# samrtbox.net
KiCad netlist of a schematic drawn in Altium Designer
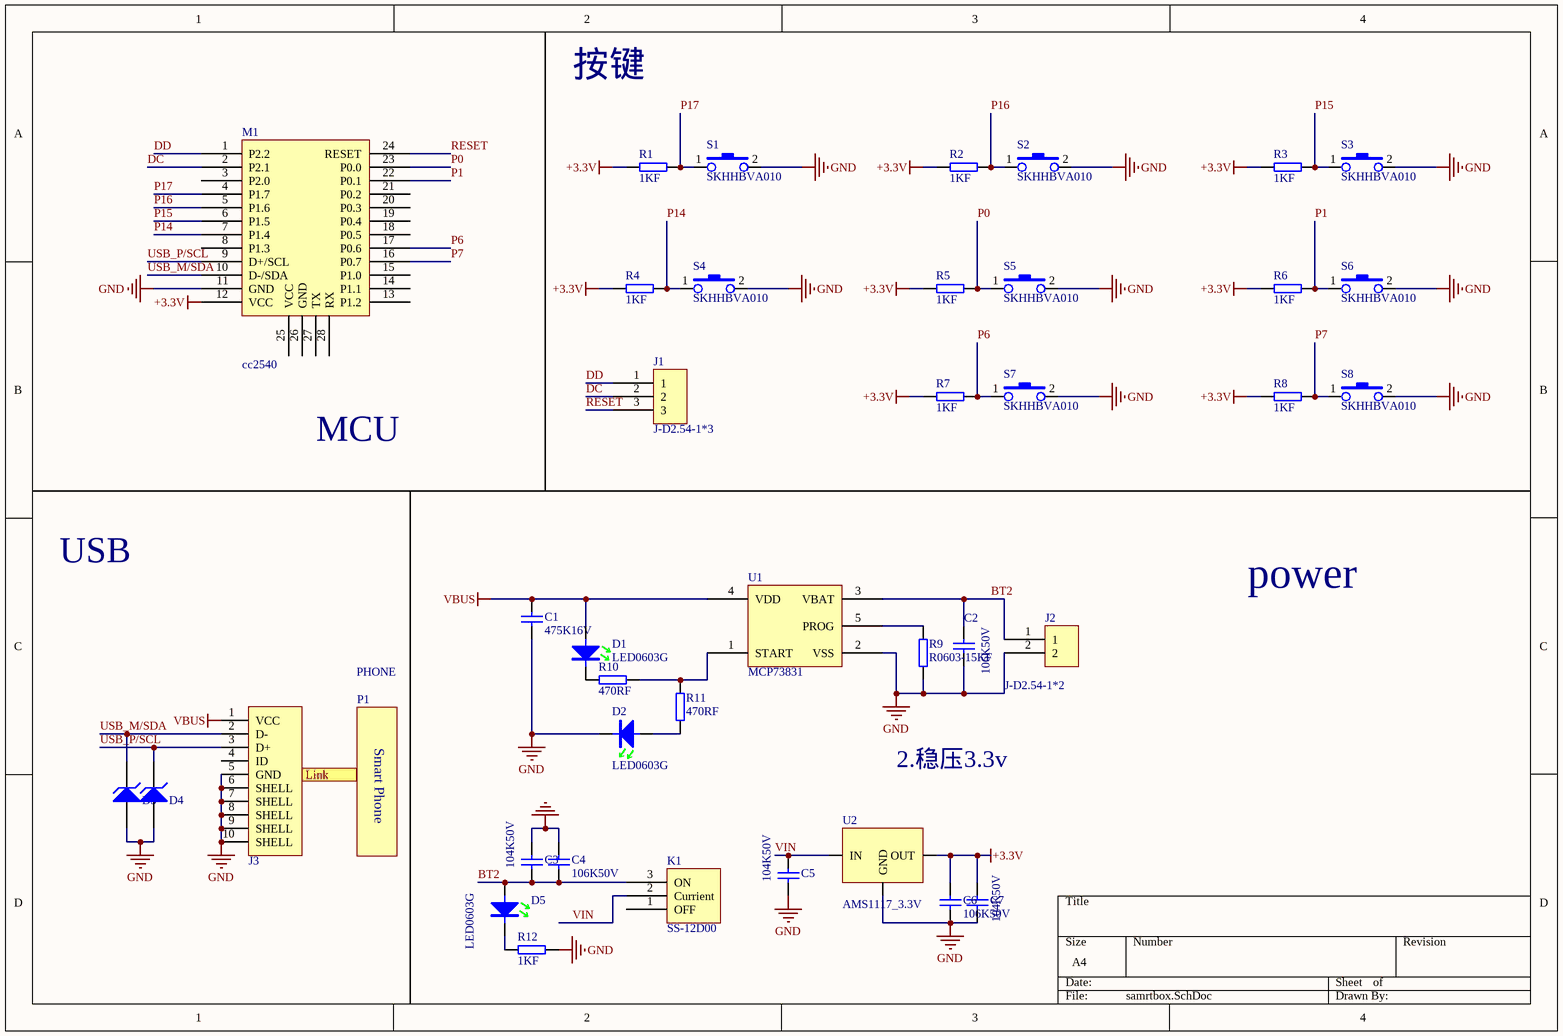
[diagram p0: samrtbox.SchDoc]

(export (version "E")
  (design (tool "Eeschema 10.0.6"))
  (components
    (comp (ref "C1")
      (value "475K16V")
      (footprint "C0603")
      (description "贴片电容-陶瓷")
      (libsource (lib "Capacitor") (part "C0603X7R-475K16V"))
    )
    (comp (ref "C2")
      (value "106K50V")
      (footprint "C0603")
      (description "贴片电容-陶瓷")
      (libsource (lib "Capacitor") (part "C0603X7R-106K50V"))
    )
    (comp (ref "C3")
      (value "104K50V")
      (footprint "C0603")
      (description "贴片电容-陶瓷")
      (libsource (lib "Capacitor") (part "C0603X7R-104K50V"))
    )
    (comp (ref "C4")
      (value "106K50V")
      (footprint "C0603")
      (description "贴片电容-陶瓷")
      (libsource (lib "Capacitor") (part "C0603X7R-106K50V"))
    )
    (comp (ref "C5")
      (value "104K50V")
      (footprint "C0603")
      (description "贴片电容-陶瓷")
      (libsource (lib "Capacitor") (part "C0603X7R-104K50V"))
    )
    (comp (ref "C6")
      (value "106K50V")
      (footprint "C0603")
      (description "贴片电容-陶瓷")
      (libsource (lib "Capacitor") (part "C0603X7R-106K50V"))
    )
    (comp (ref "C7")
      (value "104K50V")
      (footprint "C0603")
      (description "贴片电容-陶瓷")
      (libsource (lib "Capacitor") (part "C0603X7R-104K50V"))
    )
    (comp (ref "D1")
      (value "LED0603G")
      (footprint "D-LED0603G")
      (description "贴片二极管-LED")
      (libsource (lib "Diode") (part "DLED-0603-G"))
    )
    (comp (ref "D2")
      (value "LED0603G")
      (footprint "D-LED0603G")
      (description "贴片二极管-LED")
      (libsource (lib "Diode") (part "DLED-0603-G"))
    )
    (comp (ref "D3")
      (value "ESDA_TR1/0603")
      (footprint "HS_0603D")
      (description "Zener Diode")
      (fields (field (name "PUBLISHER") "*"))
      (libsource (lib "aiwacV2.0") (part "D Zener"))
    )
    (comp (ref "D4")
      (value "ESDA_TR1/0603")
      (footprint "HS_0603D")
      (description "Zener Diode")
      (fields (field (name "PUBLISHER") "*"))
      (libsource (lib "aiwacV2.0") (part "D Zener"))
    )
    (comp (ref "D5")
      (value "LED0603G")
      (footprint "D-LED0603G")
      (description "贴片二极管-LED")
      (libsource (lib "aiwacV2.0") (part "DLED-0603-G"))
    )
    (comp (ref "J1")
      (value "J-D2.54-1*3")
      (footprint "D2.54-1*3P")
      (libsource (lib "Connector") (part "J-D2.54-1*3单排"))
    )
    (comp (ref "J2")
      (value "J-D2.54-1*2")
      (footprint "D2.54-1*2P")
      (libsource (lib "Connector") (part "J-D2.54-1*2单排"))
    )
    (comp (ref "J3")
      (value "USB-MINI-SOCKET")
      (footprint "MICRO-USB - 5.9")
      (description "USB-A卧式插座")
      (libsource (lib "epic2") (part "J-USB-MINI-SOCKET"))
    )
    (comp (ref "K1")
      (value "SS-12D00")
      (footprint "SS-12D00")
      (libsource (lib "Key") (part "SS-12D00(1P2T) 立式 柄高5MM"))
    )
    (comp (ref "M1") (value "cc2540") (footprint "CC25XXSM") (libsource (lib "diapers1") (part "cc2540")))
    (comp (ref "P1") (value "PHONE") (libsource (lib "epic") (part "PHONE")))
    (comp (ref "R1")
      (value "1KF")
      (footprint "R0603")
      (description "贴片电阻-通用")
      (libsource (lib "diapers_1") (part "R0603-1KF"))
    )
    (comp (ref "R2")
      (value "1KF")
      (footprint "R0603")
      (description "贴片电阻-通用")
      (libsource (lib "diapers_1") (part "R0603-1KF"))
    )
    (comp (ref "R3")
      (value "1KF")
      (footprint "R0603")
      (description "贴片电阻-通用")
      (libsource (lib "diapers_1") (part "R0603-1KF"))
    )
    (comp (ref "R4")
      (value "1KF")
      (footprint "R0603")
      (description "贴片电阻-通用")
      (libsource (lib "diapers_1") (part "R0603-1KF"))
    )
    (comp (ref "R5")
      (value "1KF")
      (footprint "R0603")
      (description "贴片电阻-通用")
      (libsource (lib "diapers_1") (part "R0603-1KF"))
    )
    (comp (ref "R6")
      (value "1KF")
      (footprint "R0603")
      (description "贴片电阻-通用")
      (libsource (lib "diapers_1") (part "R0603-1KF"))
    )
    (comp (ref "R7")
      (value "1KF")
      (footprint "R0603")
      (description "贴片电阻-通用")
      (libsource (lib "diapers_1") (part "R0603-1KF"))
    )
    (comp (ref "R8")
      (value "1KF")
      (footprint "R0603")
      (description "贴片电阻-通用")
      (libsource (lib "diapers_1") (part "R0603-1KF"))
    )
    (comp (ref "R9")
      (value "R0603-15KF")
      (footprint "R0603")
      (description "贴片电容-通用")
      (libsource (lib "Resistor") (part "R0603-15KF"))
    )
    (comp (ref "R10")
      (value "470RF")
      (footprint "R0603")
      (description "贴片电阻-通用")
      (libsource (lib "Resistor") (part "R0603-470RF"))
    )
    (comp (ref "R11")
      (value "470RF")
      (footprint "R0603")
      (description "贴片电阻-通用")
      (libsource (lib "Resistor") (part "R0603-470RF"))
    )
    (comp (ref "R12")
      (value "1KF")
      (footprint "R0603")
      (description "贴片电阻-通用")
      (libsource (lib "Resistor") (part "R0603-1KF"))
    )
    (comp (ref "S1")
      (value "SKHHBVA010")
      (footprint "S-SKHHBVA010")
      (description "轻触按键")
      (libsource (lib "Key") (part "S-SKHHBVA010"))
    )
    (comp (ref "S2")
      (value "SKHHBVA010")
      (footprint "S-SKHHBVA010")
      (description "轻触按键")
      (libsource (lib "Key") (part "S-SKHHBVA010"))
    )
    (comp (ref "S3")
      (value "SKHHBVA010")
      (footprint "S-SKHHBVA010")
      (description "轻触按键")
      (libsource (lib "Key") (part "S-SKHHBVA010"))
    )
    (comp (ref "S4")
      (value "SKHHBVA010")
      (footprint "S-SKHHBVA010")
      (description "轻触按键")
      (libsource (lib "Key") (part "S-SKHHBVA010"))
    )
    (comp (ref "S5")
      (value "SKHHBVA010")
      (footprint "S-SKHHBVA010")
      (description "轻触按键")
      (libsource (lib "Key") (part "S-SKHHBVA010"))
    )
    (comp (ref "S6")
      (value "SKHHBVA010")
      (footprint "S-SKHHBVA010")
      (description "轻触按键")
      (libsource (lib "Key") (part "S-SKHHBVA010"))
    )
    (comp (ref "S7")
      (value "SKHHBVA010")
      (footprint "S-SKHHBVA010")
      (description "轻触按键")
      (libsource (lib "Key") (part "S-SKHHBVA010"))
    )
    (comp (ref "S8")
      (value "SKHHBVA010")
      (footprint "S-SKHHBVA010")
      (description "轻触按键")
      (libsource (lib "Key") (part "S-SKHHBVA010"))
    )
    (comp (ref "U1")
      (value "MCP73831")
      (footprint "SOT23-5N")
      (description "charge IC")
      (libsource (lib "IC") (part "MCP73831"))
    )
    (comp (ref "U2")
      (value "AMS1117_3.3V")
      (footprint "SOT-223")
      (libsource (lib "IC") (part "AMS1117-3.3V"))
    )
  )
  (nets
    (net (code "1") (name "+3.3V") (class "Default")
      (node (ref "C6") (pin "2") (pinfunction "2_2") (pintype "passive"))
      (node (ref "C7") (pin "1") (pinfunction "1_1") (pintype "passive"))
      (node (ref "M1") (pin "12") (pinfunction "VCC_12") (pintype "passive"))
      (node (ref "R1") (pin "1") (pinfunction "1_1") (pintype "passive"))
      (node (ref "R2") (pin "1") (pinfunction "1_1") (pintype "passive"))
      (node (ref "R3") (pin "1") (pinfunction "1_1") (pintype "passive"))
      (node (ref "R4") (pin "1") (pinfunction "1_1") (pintype "passive"))
      (node (ref "R5") (pin "1") (pinfunction "1_1") (pintype "passive"))
      (node (ref "R6") (pin "1") (pinfunction "1_1") (pintype "passive"))
      (node (ref "R7") (pin "1") (pinfunction "1_1") (pintype "passive"))
      (node (ref "R8") (pin "1") (pinfunction "1_1") (pintype "passive"))
      (node (ref "U2") (pin "2") (pinfunction "OUT_2") (pintype "passive"))
    )
    (net (code "2") (name "/BT2") (class "Default")
      (node (ref "C2") (pin "1") (pinfunction "1_1") (pintype "passive"))
      (node (ref "C3") (pin "2") (pinfunction "2_2") (pintype "passive"))
      (node (ref "C4") (pin "1") (pinfunction "1_1") (pintype "passive"))
      (node (ref "D5") (pin "1") (pinfunction "1_1") (pintype "passive"))
      (node (ref "J2") (pin "1") (pinfunction "1_1") (pintype "passive"))
      (node (ref "K1") (pin "3") (pinfunction "ON_3") (pintype "passive"))
      (node (ref "U1") (pin "3") (pinfunction "VBAT_3") (pintype "passive"))
    )
    (net (code "3") (name "/DC") (class "Default")
      (node (ref "J1") (pin "2") (pinfunction "2_2") (pintype "passive"))
      (node (ref "M1") (pin "2") (pinfunction "P2.1_2") (pintype "passive"))
    )
    (net (code "4") (name "/DD") (class "Default")
      (node (ref "J1") (pin "1") (pinfunction "1_1") (pintype "passive"))
      (node (ref "M1") (pin "1") (pinfunction "P2.2_1") (pintype "passive"))
    )
    (net (code "6") (name "/P0") (class "Default")
      (node (ref "M1") (pin "23") (pinfunction "P0.0_23") (pintype "passive"))
      (node (ref "R5") (pin "2") (pinfunction "2_2") (pintype "passive"))
      (node (ref "S5") (pin "1") (pinfunction "1_1") (pintype "passive"))
    )
    (net (code "7") (name "/P1") (class "Default")
      (node (ref "M1") (pin "22") (pinfunction "P0.1_22") (pintype "passive"))
      (node (ref "R6") (pin "2") (pinfunction "2_2") (pintype "passive"))
      (node (ref "S6") (pin "1") (pinfunction "1_1") (pintype "passive"))
    )
    (net (code "8") (name "/P6") (class "Default")
      (node (ref "M1") (pin "17") (pinfunction "P0.6_17") (pintype "passive"))
      (node (ref "R7") (pin "2") (pinfunction "2_2") (pintype "passive"))
      (node (ref "S7") (pin "1") (pinfunction "1_1") (pintype "passive"))
    )
    (net (code "9") (name "/P7") (class "Default")
      (node (ref "M1") (pin "16") (pinfunction "P0.7_16") (pintype "passive"))
      (node (ref "R8") (pin "2") (pinfunction "2_2") (pintype "passive"))
      (node (ref "S8") (pin "1") (pinfunction "1_1") (pintype "passive"))
    )
    (net (code "10") (name "/P14") (class "Default")
      (node (ref "M1") (pin "7") (pinfunction "P1.4_7") (pintype "passive"))
      (node (ref "R4") (pin "2") (pinfunction "2_2") (pintype "passive"))
      (node (ref "S4") (pin "1") (pinfunction "1_1") (pintype "passive"))
    )
    (net (code "11") (name "/P15") (class "Default")
      (node (ref "M1") (pin "6") (pinfunction "P1.5_6") (pintype "passive"))
      (node (ref "R3") (pin "2") (pinfunction "2_2") (pintype "passive"))
      (node (ref "S3") (pin "1") (pinfunction "1_1") (pintype "passive"))
    )
    (net (code "12") (name "/P16") (class "Default")
      (node (ref "M1") (pin "5") (pinfunction "P1.6_5") (pintype "passive"))
      (node (ref "R2") (pin "2") (pinfunction "2_2") (pintype "passive"))
      (node (ref "S2") (pin "1") (pinfunction "1_1") (pintype "passive"))
    )
    (net (code "13") (name "/P17") (class "Default")
      (node (ref "M1") (pin "4") (pinfunction "P1.7_4") (pintype "passive"))
      (node (ref "R1") (pin "2") (pinfunction "2_2") (pintype "passive"))
      (node (ref "S1") (pin "1") (pinfunction "1_1") (pintype "passive"))
    )
    (net (code "14") (name "/RESET") (class "Default")
      (node (ref "J1") (pin "3") (pinfunction "3_3") (pintype "passive"))
      (node (ref "M1") (pin "24") (pinfunction "RESET_24") (pintype "passive"))
    )
    (net (code "15") (name "/USB_M{slash}SDA") (class "Default")
      (node (ref "D3") (pin "2") (pinfunction "K_2") (pintype "passive"))
      (node (ref "J3") (pin "2") (pinfunction "D-_2") (pintype "passive"))
      (node (ref "M1") (pin "10") (pinfunction "D-/SDA_10") (pintype "passive"))
    )
    (net (code "16") (name "/USB_P{slash}SCL") (class "Default")
      (node (ref "D4") (pin "2") (pinfunction "K_2") (pintype "passive"))
      (node (ref "J3") (pin "3") (pinfunction "D+_3") (pintype "passive"))
      (node (ref "M1") (pin "9") (pinfunction "D+/SCL_9") (pintype "passive"))
    )
    (net (code "17") (name "/VIN") (class "Default")
      (node (ref "C5") (pin "1") (pinfunction "1_1") (pintype "passive"))
      (node (ref "K1") (pin "2") (pinfunction "Currient_2") (pintype "passive"))
      (node (ref "U2") (pin "3") (pinfunction "IN_3") (pintype "passive"))
    )
    (net (code "18") (name "GND") (class "Default")
      (node (ref "C1") (pin "2") (pinfunction "2_2") (pintype "passive"))
      (node (ref "C2") (pin "2") (pinfunction "2_2") (pintype "passive"))
      (node (ref "C3") (pin "1") (pinfunction "1_1") (pintype "passive"))
      (node (ref "C4") (pin "2") (pinfunction "2_2") (pintype "passive"))
      (node (ref "C5") (pin "2") (pinfunction "2_2") (pintype "passive"))
      (node (ref "C6") (pin "1") (pinfunction "1_1") (pintype "passive"))
      (node (ref "C7") (pin "2") (pinfunction "2_2") (pintype "passive"))
      (node (ref "D2") (pin "2") (pinfunction "2_2") (pintype "passive"))
      (node (ref "D3") (pin "1") (pinfunction "A_1") (pintype "passive"))
      (node (ref "D4") (pin "1") (pinfunction "A_1") (pintype "passive"))
      (node (ref "J2") (pin "2") (pinfunction "2_2") (pintype "passive"))
      (node (ref "J3") (pin "10") (pinfunction "SHELL_10") (pintype "passive"))
      (node (ref "J3") (pin "5") (pinfunction "GND_5") (pintype "passive"))
      (node (ref "J3") (pin "6") (pinfunction "SHELL_6") (pintype "passive"))
      (node (ref "J3") (pin "7") (pinfunction "SHELL_7") (pintype "passive"))
      (node (ref "J3") (pin "8") (pinfunction "SHELL_8") (pintype "passive"))
      (node (ref "J3") (pin "9") (pinfunction "SHELL_9") (pintype "passive"))
      (node (ref "M1") (pin "11") (pinfunction "GND_11") (pintype "passive"))
      (node (ref "R12") (pin "2") (pinfunction "2_2") (pintype "passive"))
      (node (ref "R9") (pin "1") (pinfunction "1_1") (pintype "passive"))
      (node (ref "S1") (pin "2") (pinfunction "2_2") (pintype "passive"))
      (node (ref "S2") (pin "2") (pinfunction "2_2") (pintype "passive"))
      (node (ref "S3") (pin "2") (pinfunction "2_2") (pintype "passive"))
      (node (ref "S4") (pin "2") (pinfunction "2_2") (pintype "passive"))
      (node (ref "S5") (pin "2") (pinfunction "2_2") (pintype "passive"))
      (node (ref "S6") (pin "2") (pinfunction "2_2") (pintype "passive"))
      (node (ref "S7") (pin "2") (pinfunction "2_2") (pintype "passive"))
      (node (ref "S8") (pin "2") (pinfunction "2_2") (pintype "passive"))
      (node (ref "U1") (pin "2") (pinfunction "VSS_2") (pintype "passive"))
      (node (ref "U2") (pin "1") (pinfunction "GND_1") (pintype "passive"))
    )
    (net (code "19") (name "Net-(D1-Pad2)") (class "Default")
      (node (ref "D1") (pin "2") (pinfunction "2_2") (pintype "passive"))
      (node (ref "R10") (pin "1") (pinfunction "1_1") (pintype "passive"))
    )
    (net (code "20") (name "Net-(D2-Pad1)") (class "Default")
      (node (ref "D2") (pin "1") (pinfunction "1_1") (pintype "passive"))
      (node (ref "R11") (pin "1") (pinfunction "1_1") (pintype "passive"))
    )
    (net (code "21") (name "Net-(D5-Pad2)") (class "Default")
      (node (ref "D5") (pin "2") (pinfunction "2_2") (pintype "passive"))
      (node (ref "R12") (pin "1") (pinfunction "1_1") (pintype "passive"))
    )
    (net (code "22") (name "Net-(U1-PROG)") (class "Default")
      (node (ref "R9") (pin "2") (pinfunction "2_2") (pintype "passive"))
      (node (ref "U1") (pin "5") (pinfunction "PROG_5") (pintype "passive"))
    )
    (net (code "23") (name "Net-(U1-START)") (class "Default")
      (node (ref "R10") (pin "2") (pinfunction "2_2") (pintype "passive"))
      (node (ref "R11") (pin "2") (pinfunction "2_2") (pintype "passive"))
      (node (ref "U1") (pin "1") (pinfunction "START_1") (pintype "passive"))
    )
    (net (code "24") (name "VBUS") (class "Default")
      (node (ref "C1") (pin "1") (pinfunction "1_1") (pintype "passive"))
      (node (ref "D1") (pin "1") (pinfunction "1_1") (pintype "passive"))
      (node (ref "J3") (pin "1") (pinfunction "VCC_1") (pintype "passive"))
      (node (ref "U1") (pin "4") (pinfunction "VDD_4") (pintype "passive"))
    )
    (net (code "25") (name "unconnected-(J3-ID-Pad4)") (class "Default")
      (node (ref "J3") (pin "4") (pinfunction "ID_4") (pintype "passive"))
    )
    (net (code "26") (name "unconnected-(K1-OFF-Pad1)") (class "Default")
      (node (ref "K1") (pin "1") (pinfunction "OFF_1") (pintype "passive"))
    )
    (net (code "27") (name "unconnected-(M1-GND-Pad26)") (class "Default")
      (node (ref "M1") (pin "26") (pinfunction "GND_26") (pintype "passive"))
    )
    (net (code "28") (name "unconnected-(M1-P0.2-Pad21)") (class "Default")
      (node (ref "M1") (pin "21") (pinfunction "P0.2_21") (pintype "passive"))
    )
    (net (code "29") (name "unconnected-(M1-P0.3-Pad20)") (class "Default")
      (node (ref "M1") (pin "20") (pinfunction "P0.3_20") (pintype "passive"))
    )
    (net (code "30") (name "unconnected-(M1-P0.4-Pad19)") (class "Default")
      (node (ref "M1") (pin "19") (pinfunction "P0.4_19") (pintype "passive"))
    )
    (net (code "31") (name "unconnected-(M1-P0.5-Pad18)") (class "Default")
      (node (ref "M1") (pin "18") (pinfunction "P0.5_18") (pintype "passive"))
    )
    (net (code "32") (name "unconnected-(M1-P1.0-Pad15)") (class "Default")
      (node (ref "M1") (pin "15") (pinfunction "P1.0_15") (pintype "passive"))
    )
    (net (code "33") (name "unconnected-(M1-P1.1-Pad14)") (class "Default")
      (node (ref "M1") (pin "14") (pinfunction "P1.1_14") (pintype "passive"))
    )
    (net (code "34") (name "unconnected-(M1-P1.2-Pad13)") (class "Default")
      (node (ref "M1") (pin "13") (pinfunction "P1.2_13") (pintype "passive"))
    )
    (net (code "35") (name "unconnected-(M1-P1.3-Pad8)") (class "Default")
      (node (ref "M1") (pin "8") (pinfunction "P1.3_8") (pintype "passive"))
    )
    (net (code "36") (name "unconnected-(M1-P2.0-Pad3)") (class "Default")
      (node (ref "M1") (pin "3") (pinfunction "P2.0_3") (pintype "passive"))
    )
    (net (code "37") (name "unconnected-(M1-RX-Pad28)") (class "Default")
      (node (ref "M1") (pin "28") (pinfunction "RX_28") (pintype "passive"))
    )
    (net (code "38") (name "unconnected-(M1-TX-Pad27)") (class "Default")
      (node (ref "M1") (pin "27") (pinfunction "TX_27") (pintype "passive"))
    )
    (net (code "39") (name "unconnected-(M1-VCC-Pad25)") (class "Default")
      (node (ref "M1") (pin "25") (pinfunction "VCC_25") (pintype "passive"))
    )
  )
)
